# powersupply.net
KiCad netlist of a schematic drawn in Altium Designer
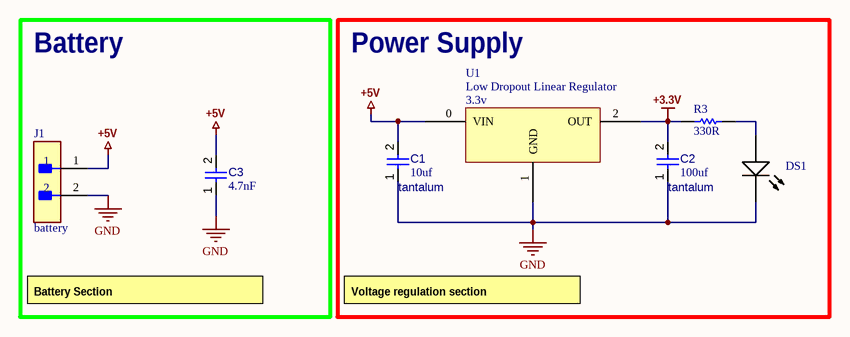
[diagram p0: powersupply.SchDoc]

(export (version "E")
  (design (tool "Eeschema 10.0.6"))
  (components
    (comp (ref "C1")
      (value "tantalum")
      (footprint "CAPC0603(1608)100_L")
      (description "Chip Capacitor, 4.7µF +/-20%, 10V, 0603, Thickness 1 mm")
      (fields (field (name "TOLERANCE") "10%") (field (name "ALTIUM_VALUE") "10uf"))
      (libsource (lib "Altium Cloud") (part "CAP-NP-2"))
    )
    (comp (ref "C2")
      (value "tantalum")
      (footprint "CAPC0603(1608)100_L")
      (description "Chip Capacitor, 4.7µF +/-20%, 10V, 0603, Thickness 1 mm")
      (fields (field (name "TOLERANCE") "10%") (field (name "ALTIUM_VALUE") "100uf"))
      (libsource (lib "Altium Cloud") (part "CAP-NP-2"))
    )
    (comp (ref "C3")
      (value "4.7nF")
      (footprint "CAPC0603(1608)100_L")
      (description "Chip Capacitor, 4.7µF +/-20%, 10V, 0603, Thickness 1 mm")
      (fields (field (name "TOLERANCE") "10%") (field (name "Comment") "Capacitor 4.7µF +/-20% 10V 0603"))
      (libsource (lib "Altium Cloud") (part "CAP-NP-2"))
    )
    (comp (ref "DS1")
      (value "16-219A/T2D-AR2T1QY/3T")
      (footprint "EVRL-0402-2_V")
      (description "Chip LED, White, 5 V, 10 mA, 30 mW, -40 to 85 degC, 2-Pin SMD (0402), RoHS, Tape and Reel")
      (fields (field (name "POWER") "30mW") (field (name "MANUFACTURER") "Everlight Electronics"))
      (libsource (lib "Altium Cloud") (part "LED-WHITE-AK-2"))
    )
    (comp (ref "J1")
      (value "battery")
      (footprint "FP-TMM-102-03-T-S-MFG")
      (description "CONN HEADER VERT 2POS 2MM")
      (libsource (lib "Altium Content Vault") (part "3bc925449376181038e59eaffc5286c"))
    )
    (comp (ref "R3")
      (value "330R")
      (footprint "RESC1608X55X25ML10T15")
      (description "Chip Resistor, 0 Ohm, 0.1 W, -55 to 155 degC, 0603 (1608 Metric)")
      (fields (field (name "POWER") "100mW") (field (name "TOLERANCE") "5%"))
      (libsource (lib "Altium Cloud") (part "RES-2"))
    )
    (comp (ref "U1")
      (value "Low Dropout Linear Regulator")
      (footprint "4 pin SOT")
      (fields (field (name "OUTPUT VOLATGE") "3.3v"))
      (libsource (lib "Schlib1") (part "lm1117"))
    )
  )
  (nets
    (net (code "1") (name "+3.3V") (class "Default")
      (node (ref "C2") (pin "2") (pinfunction "2_2") (pintype "passive"))
      (node (ref "R3") (pin "1") (pinfunction "1_1") (pintype "passive"))
      (node (ref "U1") (pin "2") (pinfunction "OUT_2") (pintype "passive"))
    )
    (net (code "2") (name "+5V") (class "Default")
      (node (ref "C1") (pin "2") (pinfunction "2_2") (pintype "passive"))
      (node (ref "C3") (pin "2") (pinfunction "2_2") (pintype "passive"))
      (node (ref "J1") (pin "1") (pinfunction "1_1") (pintype "passive"))
      (node (ref "U1") (pin "0") (pinfunction "VIN_0") (pintype "passive"))
    )
    (net (code "3") (name "GND") (class "Default")
      (node (ref "C1") (pin "1") (pinfunction "1_1") (pintype "passive"))
      (node (ref "C2") (pin "1") (pinfunction "1_1") (pintype "passive"))
      (node (ref "C3") (pin "1") (pinfunction "1_1") (pintype "passive"))
      (node (ref "DS1") (pin "2") (pinfunction "K_2") (pintype "passive"))
      (node (ref "J1") (pin "2") (pinfunction "2_2") (pintype "passive"))
      (node (ref "U1") (pin "1") (pinfunction "GND_1") (pintype "passive"))
    )
    (net (code "4") (name "Net-(DS1-A)") (class "Default")
      (node (ref "DS1") (pin "1") (pinfunction "A_1") (pintype "passive"))
      (node (ref "R3") (pin "2") (pinfunction "2_2") (pintype "passive"))
    )
  )
)
